# yard-ice-fpga-pwr.net
KiCad netlist of a schematic drawn in Altium Designer
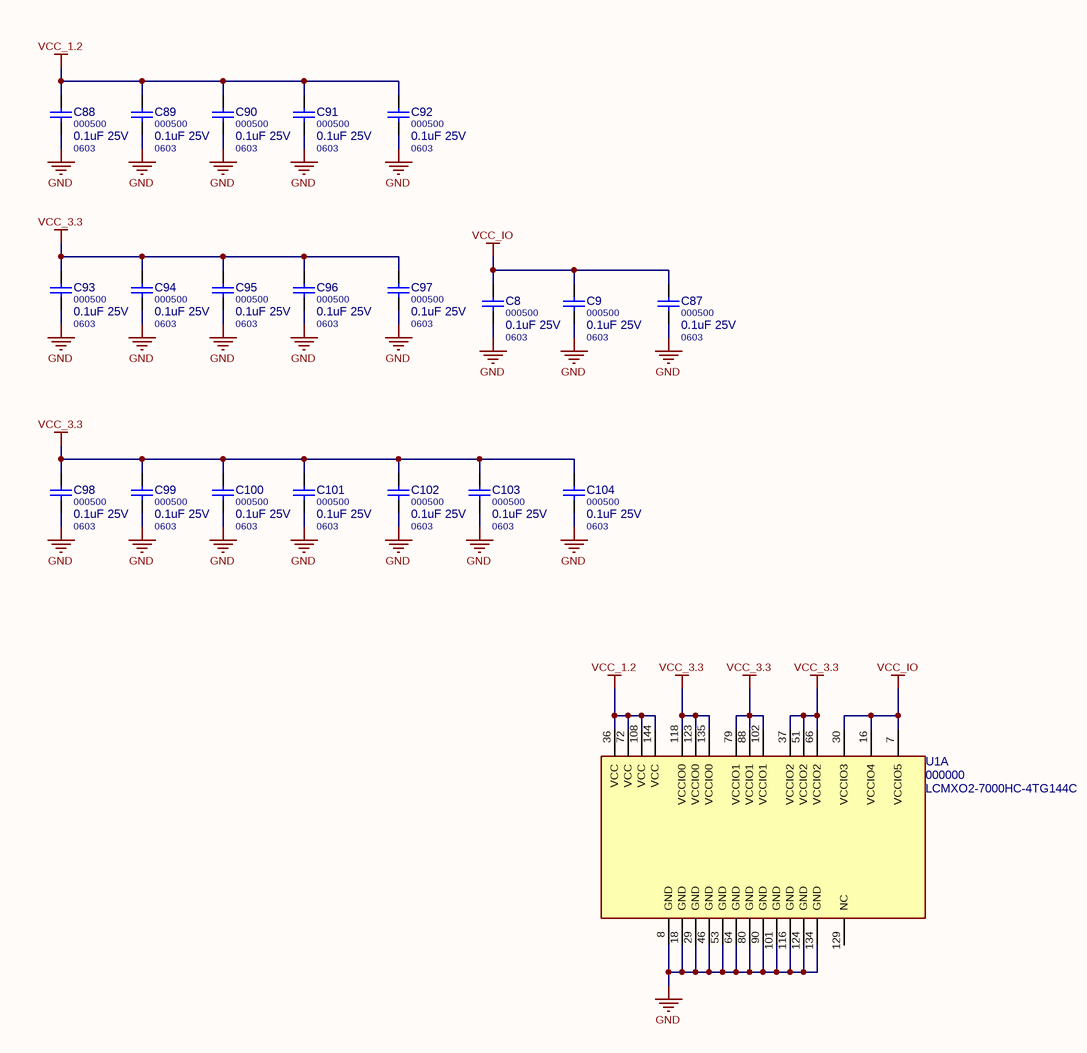
[diagram p0: yard-ice-fpga-pwr.SchDoc]

(export (version "E")
  (design (tool "Eeschema 10.0.6"))
  (components
    (comp (ref "C8")
      (value "000500")
      (footprint "C0603M")
      (description "SMD Ceramic Chip Capacitor - 0603 - X7R")
      (fields
        (field (name "ALTIUM_VALUE") "0.1uF 25V")
        (field (name "PACKAGE") "0603")
        (field (name "MF") "TDK")
      )
      (libsource (lib "discrete-sm") (part "C0603"))
    )
    (comp (ref "C9")
      (value "000500")
      (footprint "C0603M")
      (description "SMD Ceramic Chip Capacitor - 0603 - X7R")
      (fields
        (field (name "ALTIUM_VALUE") "0.1uF 25V")
        (field (name "PACKAGE") "0603")
        (field (name "MF") "TDK")
      )
      (libsource (lib "discrete-sm") (part "C0603"))
    )
    (comp (ref "C87")
      (value "000500")
      (footprint "C0603M")
      (description "SMD Ceramic Chip Capacitor - 0603 - X7R")
      (fields
        (field (name "ALTIUM_VALUE") "0.1uF 25V")
        (field (name "PACKAGE") "0603")
        (field (name "MF") "TDK")
      )
      (libsource (lib "discrete-sm") (part "C0603"))
    )
    (comp (ref "C88")
      (value "000500")
      (footprint "C0603M")
      (description "SMD Ceramic Chip Capacitor - 0603 - X7R")
      (fields
        (field (name "ALTIUM_VALUE") "0.1uF 25V")
        (field (name "PACKAGE") "0603")
        (field (name "MF") "TDK")
      )
      (libsource (lib "discrete-sm") (part "C0603"))
    )
    (comp (ref "C89")
      (value "000500")
      (footprint "C0603M")
      (description "SMD Ceramic Chip Capacitor - 0603 - X7R")
      (fields
        (field (name "ALTIUM_VALUE") "0.1uF 25V")
        (field (name "PACKAGE") "0603")
        (field (name "MF") "TDK")
      )
      (libsource (lib "discrete-sm") (part "C0603"))
    )
    (comp (ref "C90")
      (value "000500")
      (footprint "C0603M")
      (description "SMD Ceramic Chip Capacitor - 0603 - X7R")
      (fields
        (field (name "ALTIUM_VALUE") "0.1uF 25V")
        (field (name "PACKAGE") "0603")
        (field (name "MF") "TDK")
      )
      (libsource (lib "discrete-sm") (part "C0603"))
    )
    (comp (ref "C91")
      (value "000500")
      (footprint "C0603M")
      (description "SMD Ceramic Chip Capacitor - 0603 - X7R")
      (fields
        (field (name "ALTIUM_VALUE") "0.1uF 25V")
        (field (name "PACKAGE") "0603")
        (field (name "MF") "TDK")
      )
      (libsource (lib "discrete-sm") (part "C0603"))
    )
    (comp (ref "C92")
      (value "000500")
      (footprint "C0603M")
      (description "SMD Ceramic Chip Capacitor - 0603 - X7R")
      (fields
        (field (name "ALTIUM_VALUE") "0.1uF 25V")
        (field (name "PACKAGE") "0603")
        (field (name "MF") "TDK")
      )
      (libsource (lib "discrete-sm") (part "C0603"))
    )
    (comp (ref "C93")
      (value "000500")
      (footprint "C0603M")
      (description "SMD Ceramic Chip Capacitor - 0603 - X7R")
      (fields
        (field (name "ALTIUM_VALUE") "0.1uF 25V")
        (field (name "PACKAGE") "0603")
        (field (name "MF") "TDK")
      )
      (libsource (lib "discrete-sm") (part "C0603"))
    )
    (comp (ref "C94")
      (value "000500")
      (footprint "C0603M")
      (description "SMD Ceramic Chip Capacitor - 0603 - X7R")
      (fields
        (field (name "ALTIUM_VALUE") "0.1uF 25V")
        (field (name "PACKAGE") "0603")
        (field (name "MF") "TDK")
      )
      (libsource (lib "discrete-sm") (part "C0603"))
    )
    (comp (ref "C95")
      (value "000500")
      (footprint "C0603M")
      (description "SMD Ceramic Chip Capacitor - 0603 - X7R")
      (fields
        (field (name "ALTIUM_VALUE") "0.1uF 25V")
        (field (name "PACKAGE") "0603")
        (field (name "MF") "TDK")
      )
      (libsource (lib "discrete-sm") (part "C0603"))
    )
    (comp (ref "C96")
      (value "000500")
      (footprint "C0603M")
      (description "SMD Ceramic Chip Capacitor - 0603 - X7R")
      (fields
        (field (name "ALTIUM_VALUE") "0.1uF 25V")
        (field (name "PACKAGE") "0603")
        (field (name "MF") "TDK")
      )
      (libsource (lib "discrete-sm") (part "C0603"))
    )
    (comp (ref "C97")
      (value "000500")
      (footprint "C0603M")
      (description "SMD Ceramic Chip Capacitor - 0603 - X7R")
      (fields
        (field (name "ALTIUM_VALUE") "0.1uF 25V")
        (field (name "PACKAGE") "0603")
        (field (name "MF") "TDK")
      )
      (libsource (lib "discrete-sm") (part "C0603"))
    )
    (comp (ref "C98")
      (value "000500")
      (footprint "C0603M")
      (description "SMD Ceramic Chip Capacitor - 0603 - X7R")
      (fields
        (field (name "ALTIUM_VALUE") "0.1uF 25V")
        (field (name "PACKAGE") "0603")
        (field (name "MF") "TDK")
      )
      (libsource (lib "discrete-sm") (part "C0603"))
    )
    (comp (ref "C99")
      (value "000500")
      (footprint "C0603M")
      (description "SMD Ceramic Chip Capacitor - 0603 - X7R")
      (fields
        (field (name "ALTIUM_VALUE") "0.1uF 25V")
        (field (name "PACKAGE") "0603")
        (field (name "MF") "TDK")
      )
      (libsource (lib "discrete-sm") (part "C0603"))
    )
    (comp (ref "C100")
      (value "000500")
      (footprint "C0603M")
      (description "SMD Ceramic Chip Capacitor - 0603 - X7R")
      (fields
        (field (name "ALTIUM_VALUE") "0.1uF 25V")
        (field (name "PACKAGE") "0603")
        (field (name "MF") "TDK")
      )
      (libsource (lib "discrete-sm") (part "C0603"))
    )
    (comp (ref "C101")
      (value "000500")
      (footprint "C0603M")
      (description "SMD Ceramic Chip Capacitor - 0603 - X7R")
      (fields
        (field (name "ALTIUM_VALUE") "0.1uF 25V")
        (field (name "PACKAGE") "0603")
        (field (name "MF") "TDK")
      )
      (libsource (lib "discrete-sm") (part "C0603"))
    )
    (comp (ref "C102")
      (value "000500")
      (footprint "C0603M")
      (description "SMD Ceramic Chip Capacitor - 0603 - X7R")
      (fields
        (field (name "ALTIUM_VALUE") "0.1uF 25V")
        (field (name "PACKAGE") "0603")
        (field (name "MF") "TDK")
      )
      (libsource (lib "discrete-sm") (part "C0603"))
    )
    (comp (ref "C103")
      (value "000500")
      (footprint "C0603M")
      (description "SMD Ceramic Chip Capacitor - 0603 - X7R")
      (fields
        (field (name "ALTIUM_VALUE") "0.1uF 25V")
        (field (name "PACKAGE") "0603")
        (field (name "MF") "TDK")
      )
      (libsource (lib "discrete-sm") (part "C0603"))
    )
    (comp (ref "C104")
      (value "000500")
      (footprint "C0603M")
      (description "SMD Ceramic Chip Capacitor - 0603 - X7R")
      (fields
        (field (name "ALTIUM_VALUE") "0.1uF 25V")
        (field (name "PACKAGE") "0603")
        (field (name "MF") "TDK")
      )
      (libsource (lib "discrete-sm") (part "C0603"))
    )
    (comp (ref "U1")
      (value "000000")
      (footprint "144-TQFP")
      (description "FPGA, 6864 Logic Elements, Flash")
      (fields (field (name "MF") "Lattice") (field (name "ALTIUM_VALUE") "LCMXO2-7000HC-4TG144C"))
      (libsource (lib "lattice-fpga") (part "LCMXO2-7000HC"))
    )
  )
  (nets
    (net (code "1") (name "GND") (class "Default")
      (node (ref "C100") (pin "2") (pinfunction "2_2") (pintype "passive"))
      (node (ref "C101") (pin "2") (pinfunction "2_2") (pintype "passive"))
      (node (ref "C102") (pin "2") (pinfunction "2_2") (pintype "passive"))
      (node (ref "C103") (pin "2") (pinfunction "2_2") (pintype "passive"))
      (node (ref "C104") (pin "2") (pinfunction "2_2") (pintype "passive"))
      (node (ref "C8") (pin "2") (pinfunction "2_2") (pintype "passive"))
      (node (ref "C87") (pin "2") (pinfunction "2_2") (pintype "passive"))
      (node (ref "C88") (pin "2") (pinfunction "2_2") (pintype "passive"))
      (node (ref "C89") (pin "2") (pinfunction "2_2") (pintype "passive"))
      (node (ref "C9") (pin "2") (pinfunction "2_2") (pintype "passive"))
      (node (ref "C90") (pin "2") (pinfunction "2_2") (pintype "passive"))
      (node (ref "C91") (pin "2") (pinfunction "2_2") (pintype "passive"))
      (node (ref "C92") (pin "2") (pinfunction "2_2") (pintype "passive"))
      (node (ref "C93") (pin "2") (pinfunction "2_2") (pintype "passive"))
      (node (ref "C94") (pin "2") (pinfunction "2_2") (pintype "passive"))
      (node (ref "C95") (pin "2") (pinfunction "2_2") (pintype "passive"))
      (node (ref "C96") (pin "2") (pinfunction "2_2") (pintype "passive"))
      (node (ref "C97") (pin "2") (pinfunction "2_2") (pintype "passive"))
      (node (ref "C98") (pin "2") (pinfunction "2_2") (pintype "passive"))
      (node (ref "C99") (pin "2") (pinfunction "2_2") (pintype "passive"))
      (node (ref "U1") (pin "101") (pinfunction "GND_101") (pintype "passive"))
      (node (ref "U1") (pin "116") (pinfunction "GND_116") (pintype "passive"))
      (node (ref "U1") (pin "124") (pinfunction "GND_124") (pintype "passive"))
      (node (ref "U1") (pin "134") (pinfunction "GND_134") (pintype "passive"))
      (node (ref "U1") (pin "18") (pinfunction "GND_18") (pintype "passive"))
      (node (ref "U1") (pin "29") (pinfunction "GND_29") (pintype "passive"))
      (node (ref "U1") (pin "46") (pinfunction "GND_46") (pintype "passive"))
      (node (ref "U1") (pin "53") (pinfunction "GND_53") (pintype "passive"))
      (node (ref "U1") (pin "64") (pinfunction "GND_64") (pintype "passive"))
      (node (ref "U1") (pin "8") (pinfunction "GND_8") (pintype "passive"))
      (node (ref "U1") (pin "80") (pinfunction "GND_80") (pintype "passive"))
      (node (ref "U1") (pin "90") (pinfunction "GND_90") (pintype "passive"))
    )
    (net (code "2") (name "VCC_1.2") (class "Default")
      (node (ref "C88") (pin "1") (pinfunction "1_1") (pintype "passive"))
      (node (ref "C89") (pin "1") (pinfunction "1_1") (pintype "passive"))
      (node (ref "C90") (pin "1") (pinfunction "1_1") (pintype "passive"))
      (node (ref "C91") (pin "1") (pinfunction "1_1") (pintype "passive"))
      (node (ref "C92") (pin "1") (pinfunction "1_1") (pintype "passive"))
      (node (ref "U1") (pin "108") (pinfunction "VCC_108") (pintype "passive"))
      (node (ref "U1") (pin "144") (pinfunction "VCC_144") (pintype "passive"))
      (node (ref "U1") (pin "36") (pinfunction "VCC_36") (pintype "passive"))
      (node (ref "U1") (pin "72") (pinfunction "VCC_72") (pintype "passive"))
    )
    (net (code "3") (name "VCC_3.3") (class "Default")
      (node (ref "C100") (pin "1") (pinfunction "1_1") (pintype "passive"))
      (node (ref "C101") (pin "1") (pinfunction "1_1") (pintype "passive"))
      (node (ref "C102") (pin "1") (pinfunction "1_1") (pintype "passive"))
      (node (ref "C103") (pin "1") (pinfunction "1_1") (pintype "passive"))
      (node (ref "C104") (pin "1") (pinfunction "1_1") (pintype "passive"))
      (node (ref "C93") (pin "1") (pinfunction "1_1") (pintype "passive"))
      (node (ref "C94") (pin "1") (pinfunction "1_1") (pintype "passive"))
      (node (ref "C95") (pin "1") (pinfunction "1_1") (pintype "passive"))
      (node (ref "C96") (pin "1") (pinfunction "1_1") (pintype "passive"))
      (node (ref "C97") (pin "1") (pinfunction "1_1") (pintype "passive"))
      (node (ref "C98") (pin "1") (pinfunction "1_1") (pintype "passive"))
      (node (ref "C99") (pin "1") (pinfunction "1_1") (pintype "passive"))
      (node (ref "U1") (pin "102") (pinfunction "VCCIO1_102") (pintype "passive"))
      (node (ref "U1") (pin "118") (pinfunction "VCCIO0_118") (pintype "passive"))
      (node (ref "U1") (pin "123") (pinfunction "VCCIO0_123") (pintype "passive"))
      (node (ref "U1") (pin "135") (pinfunction "VCCIO0_135") (pintype "passive"))
      (node (ref "U1") (pin "37") (pinfunction "VCCIO2_37") (pintype "passive"))
      (node (ref "U1") (pin "51") (pinfunction "VCCIO2_51") (pintype "passive"))
      (node (ref "U1") (pin "66") (pinfunction "VCCIO2_66") (pintype "passive"))
      (node (ref "U1") (pin "79") (pinfunction "VCCIO1_79") (pintype "passive"))
      (node (ref "U1") (pin "88") (pinfunction "VCCIO1_88") (pintype "power_in"))
    )
    (net (code "4") (name "VCC_IO") (class "Default")
      (node (ref "C8") (pin "1") (pinfunction "1_1") (pintype "passive"))
      (node (ref "C87") (pin "1") (pinfunction "1_1") (pintype "passive"))
      (node (ref "C9") (pin "1") (pinfunction "1_1") (pintype "passive"))
      (node (ref "U1") (pin "16") (pinfunction "VCCIO4_16") (pintype "passive"))
      (node (ref "U1") (pin "30") (pinfunction "VCCIO3_30") (pintype "passive"))
      (node (ref "U1") (pin "7") (pinfunction "VCCIO5_7") (pintype "passive"))
    )
    (net (code "5") (name "unconnected-(U1A-NC-Pad129)") (class "Default")
      (node (ref "U1") (pin "129") (pinfunction "NC_129") (pintype "passive"))
    )
  )
)
